# ADP1706_3p3.net
KiCad netlist of a schematic drawn in Altium Designer
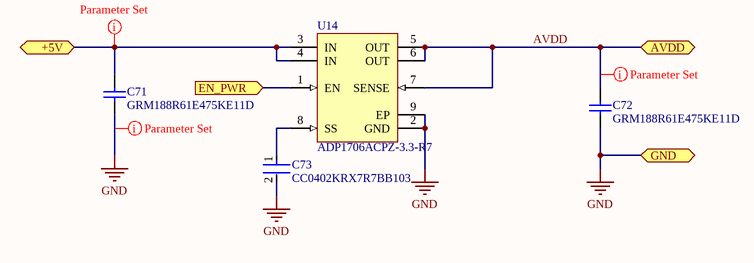
[diagram p0: ADP1706_3p3.SchDoc]

(export (version "E")
  (design (tool "Eeschema 10.0.6"))
  (components
    (comp (ref "C71")
      (value "GRM188R61E475KE11D")
      (footprint "CAPC1608X90X35LL10T15")
      (fields (field (name "MANUFACTURER") "Murata"))
      (libsource (lib "Altium Content Vault") (part "CAP"))
    )
    (comp (ref "C72")
      (value "GRM188R61E475KE11D")
      (footprint "CAPC1608X90X35LL10T15")
      (fields (field (name "MANUFACTURER") "Murata"))
      (libsource (lib "Altium Content Vault") (part "CAP"))
    )
    (comp (ref "C73")
      (value "CC0402KRX7R7BB103")
      (footprint "FP-CC0402-MFG")
      (description "CAP CER 10000PF 16V X7R 0402")
      (fields (field (name "TOLERANCE") "0.1") (field (name "MANUFACTURER") "YAGEO"))
      (libsource (lib "Altium Content Vault") (part "11868f565c42a9108669ba33697ecf6"))
    )
    (comp (ref "U14")
      (value "ADP1706ACPZ-3.3-R7")
      (footprint "ADI-CP-8-2_L")
      (fields (field (name "MANUFACTURER") "Analog Devices"))
      (libsource (lib "Altium Content Vault") (part "ADI-ADP1706-CP-8-2"))
    )
  )
  (nets
    (net (code "1") (name "/+5V") (class "Default")
      (node (ref "C71") (pin "2") (pinfunction "2_2") (pintype "passive"))
      (node (ref "U14") (pin "3") (pinfunction "IN_3") (pintype "power_in"))
      (node (ref "U14") (pin "4") (pinfunction "IN_4") (pintype "power_in"))
    )
    (net (code "2") (name "/AVDD") (class "Default")
      (node (ref "C72") (pin "2") (pinfunction "2_2") (pintype "passive"))
      (node (ref "U14") (pin "5") (pinfunction "OUT_5") (pintype "power_in"))
      (node (ref "U14") (pin "6") (pinfunction "OUT_6") (pintype "power_in"))
      (node (ref "U14") (pin "7") (pinfunction "SENSE_7") (pintype "input"))
    )
    (net (code "3") (name "/EN_PWR") (class "Default")
      (node (ref "U14") (pin "1") (pinfunction "EN_1") (pintype "input"))
    )
    (net (code "4") (name "GND") (class "Default")
      (node (ref "C71") (pin "1") (pinfunction "1_1") (pintype "passive"))
      (node (ref "C72") (pin "1") (pinfunction "1_1") (pintype "passive"))
      (node (ref "C73") (pin "2") (pinfunction "2_2") (pintype "passive"))
      (node (ref "U14") (pin "2") (pinfunction "GND_2") (pintype "power_in"))
      (node (ref "U14") (pin "9") (pinfunction "EP_9") (pintype "power_in"))
    )
    (net (code "5") (name "Net-(U14-SS)") (class "Default")
      (node (ref "C73") (pin "1") (pinfunction "1_1") (pintype "passive"))
      (node (ref "U14") (pin "8") (pinfunction "SS_8") (pintype "input"))
    )
  )
)
